# CTRL_POWER_OVER_ETHERNET.net
KiCad netlist of a schematic drawn in Altium Designer
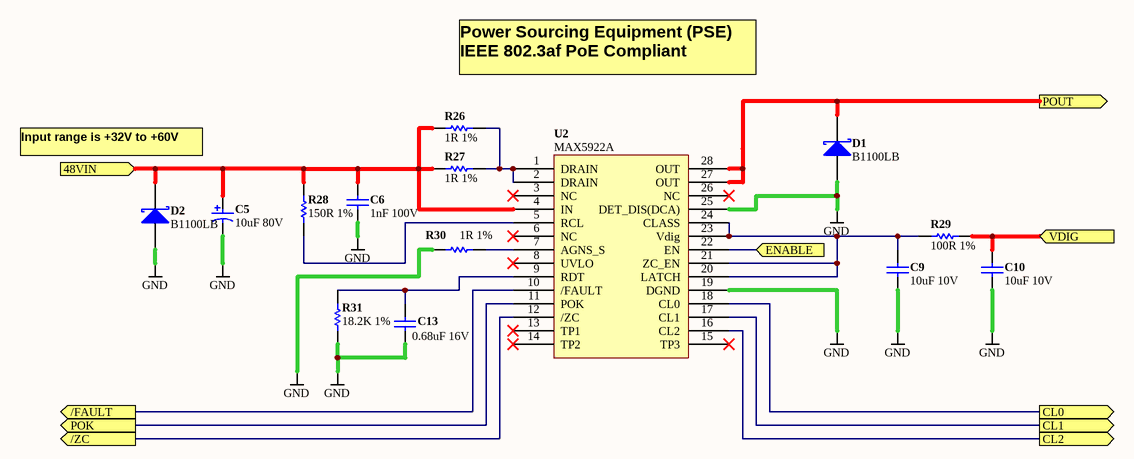
[diagram p0: CTRL_POWER_OVER_ETHERNET.SchDoc]

(export (version "E")
  (design (tool "Eeschema 10.0.6"))
  (components
    (comp (ref "C5")
      (value "10uF 80V")
      (footprint "CAP_FK_E_ELECTRO")
      (description "Capacitor, Electro, SMD, 80V, 10uF, Case E")
      (fields (field (name "TOLERANCE") "20 %"))
      (libsource (lib "AltiumDesignLibrary") (part "CAP-P"))
    )
    (comp (ref "C6")
      (value "1nF 100V")
      (footprint "CAPC2012-STAR")
      (description "Capacitor, Ceramic, 1nF, 100V, 0805, X7R")
      (fields (field (name "TOLERANCE") "%"))
      (libsource (lib "AltiumDesignLibrary") (part "CAP-NP"))
    )
    (comp (ref "C9")
      (value "10uF 10V")
      (footprint "CAPC2012-STAR")
      (description "Capacitor, Ceramic, 10uF 10% 10V 0805 (2012) X5R")
      (fields (field (name "TOLERANCE") "10 %"))
      (libsource (lib "AltiumDesignLibrary") (part "CAP-NP"))
    )
    (comp (ref "C10")
      (value "10uF 10V")
      (footprint "CAPC2012-STAR")
      (description "Capacitor, Ceramic, 10uF 10% 10V 0805 (2012) X5R")
      (fields (field (name "TOLERANCE") "10 %"))
      (libsource (lib "AltiumDesignLibrary") (part "CAP-NP"))
    )
    (comp (ref "C13")
      (value "0.68uF 16V")
      (footprint "CAPC1608-STAR")
      (description "Capacitor, Ceramic, 0.68uF 20% 16V 0603 X5R")
      (fields (field (name "TOLERANCE") "20 %"))
      (libsource (lib "AltiumDesignLibrary") (part "CAP-NP"))
    )
    (comp (ref "D1")
      (value "B1100LB")
      (footprint "DIOM8059")
      (description "Schottky Diode, 1A, 100V, SMB, B1100LB")
      (libsource (lib "AltiumDesignLibrary") (part "DIO-SCHOTTKY-1S"))
    )
    (comp (ref "D2")
      (value "B1100LB")
      (footprint "DIOM8059")
      (description "Schottky Diode, 1A, 100V, SMB, B1100LB")
      (libsource (lib "AltiumDesignLibrary") (part "DIO-SCHOTTKY-1S"))
    )
    (comp (ref "R26")
      (value "1R 1%")
      (footprint "RESC2012-STAR")
      (description "Resistor, 1R 1% 0805 (2012)")
      (fields (field (name "TOLERANCE") "1 %"))
      (libsource (lib "AltiumDesignLibrary") (part "RES"))
    )
    (comp (ref "R27")
      (value "1R 1%")
      (footprint "RESC2012-STAR")
      (description "Resistor, 1R 1% 0805 (2012)")
      (fields (field (name "TOLERANCE") "1 %"))
      (libsource (lib "AltiumDesignLibrary") (part "RES"))
    )
    (comp (ref "R28")
      (value "150R 1%")
      (footprint "RESC1005-STAR")
      (description "Resistor, 150R 1% 0402 (1005)")
      (fields (field (name "TOLERANCE") "1 %"))
      (libsource (lib "AltiumDesignLibrary") (part "RES"))
    )
    (comp (ref "R29")
      (value "100R 1%")
      (footprint "RESC1005-STAR")
      (description "Resistor, 100R 1% 0402 (1005)")
      (fields (field (name "TOLERANCE") "1 %"))
      (libsource (lib "AltiumDesignLibrary") (part "RES"))
    )
    (comp (ref "R30")
      (value "1R 1%")
      (footprint "RESC2012-STAR")
      (description "Resistor, 1R 1% 0805 (2012)")
      (fields (field (name "TOLERANCE") "1 %"))
      (libsource (lib "AltiumDesignLibrary") (part "RES"))
    )
    (comp (ref "R31")
      (value "18.2K 1%")
      (footprint "RESC1005-STAR")
      (description "Resistor, 18.2K 1% 0402 (1005)")
      (fields (field (name "TOLERANCE") "1 %"))
      (libsource (lib "AltiumDesignLibrary") (part "RES"))
    )
    (comp (ref "U2")
      (value "MAX5922A")
      (footprint "TSOP65P640-28")
      (description "MAX5922A, PoE Controller")
      (libsource (lib "AltiumDesignLibrary") (part "MAX5922"))
    )
  )
  (nets
    (net (code "1") (name "/48VIN") (class "Default")
      (node (ref "C5") (pin "1") (pinfunction "1_1") (pintype "passive"))
      (node (ref "C6") (pin "1") (pinfunction "1_1") (pintype "passive"))
      (node (ref "D2") (pin "2") (pinfunction "K_2") (pintype "passive"))
      (node (ref "R26") (pin "1") (pinfunction "1_1") (pintype "passive"))
      (node (ref "R27") (pin "1") (pinfunction "1_1") (pintype "passive"))
      (node (ref "R28") (pin "1") (pinfunction "1_1") (pintype "passive"))
      (node (ref "U2") (pin "4") (pinfunction "IN_4") (pintype "passive"))
    )
    (net (code "2") (name "/CL0") (class "Default")
      (node (ref "U2") (pin "18") (pinfunction "CL0_18") (pintype "passive"))
    )
    (net (code "3") (name "/CL1") (class "Default")
      (node (ref "U2") (pin "17") (pinfunction "CL1_17") (pintype "passive"))
    )
    (net (code "4") (name "/CL2") (class "Default")
      (node (ref "U2") (pin "16") (pinfunction "CL2_16") (pintype "passive"))
    )
    (net (code "5") (name "/ENABLE") (class "Default")
      (node (ref "U2") (pin "22") (pinfunction "EN_22") (pintype "passive"))
    )
    (net (code "6") (name "/POK") (class "Default")
      (node (ref "U2") (pin "11") (pinfunction "POK_11") (pintype "passive"))
    )
    (net (code "7") (name "/POUT") (class "Default")
      (node (ref "D1") (pin "2") (pinfunction "K_2") (pintype "passive"))
      (node (ref "U2") (pin "27") (pinfunction "OUT_27") (pintype "passive"))
      (node (ref "U2") (pin "28") (pinfunction "OUT_28") (pintype "passive"))
    )
    (net (code "8") (name "/VDIG") (class "Default")
      (node (ref "C10") (pin "1") (pinfunction "1_1") (pintype "passive"))
      (node (ref "R29") (pin "2") (pinfunction "2_2") (pintype "passive"))
    )
    (net (code "9") (name "/{slash}FAULT") (class "Default")
      (node (ref "U2") (pin "10") (pinfunction "/FAULT_10") (pintype "passive"))
    )
    (net (code "10") (name "/{slash}ZC") (class "Default")
      (node (ref "U2") (pin "12") (pinfunction "/ZC_12") (pintype "passive"))
    )
    (net (code "11") (name "GND") (class "Default")
      (node (ref "C10") (pin "2") (pinfunction "2_2") (pintype "passive"))
      (node (ref "C13") (pin "2") (pinfunction "2_2") (pintype "passive"))
      (node (ref "C5") (pin "2") (pinfunction "2_2") (pintype "passive"))
      (node (ref "C6") (pin "2") (pinfunction "2_2") (pintype "passive"))
      (node (ref "C9") (pin "2") (pinfunction "2_2") (pintype "passive"))
      (node (ref "D1") (pin "1") (pinfunction "A_1") (pintype "passive"))
      (node (ref "D2") (pin "1") (pinfunction "A_1") (pintype "passive"))
      (node (ref "R30") (pin "2") (pinfunction "2_2") (pintype "passive"))
      (node (ref "R31") (pin "2") (pinfunction "2_2") (pintype "passive"))
      (node (ref "U2") (pin "19") (pinfunction "DGND_19") (pintype "passive"))
      (node (ref "U2") (pin "25") (pinfunction "DET_DIS(DCA)_25") (pintype "passive"))
    )
    (net (code "12") (name "Net-(R26-Pad2)") (class "Default")
      (node (ref "R26") (pin "2") (pinfunction "2_2") (pintype "passive"))
      (node (ref "R27") (pin "2") (pinfunction "2_2") (pintype "passive"))
      (node (ref "U2") (pin "1") (pinfunction "DRAIN_1") (pintype "passive"))
      (node (ref "U2") (pin "2") (pinfunction "DRAIN_2") (pintype "passive"))
    )
    (net (code "13") (name "Net-(U2-AGNS_S)") (class "Default")
      (node (ref "R30") (pin "1") (pinfunction "1_1") (pintype "passive"))
      (node (ref "U2") (pin "7") (pinfunction "AGNS_S_7") (pintype "passive"))
    )
    (net (code "14") (name "Net-(U2-CLASS)") (class "Default")
      (node (ref "C9") (pin "1") (pinfunction "1_1") (pintype "passive"))
      (node (ref "R29") (pin "1") (pinfunction "1_1") (pintype "passive"))
      (node (ref "U2") (pin "20") (pinfunction "LATCH_20") (pintype "passive"))
      (node (ref "U2") (pin "21") (pinfunction "ZC_EN_21") (pintype "passive"))
      (node (ref "U2") (pin "23") (pinfunction "Vdig_23") (pintype "passive"))
      (node (ref "U2") (pin "24") (pinfunction "CLASS_24") (pintype "passive"))
    )
    (net (code "15") (name "Net-(U2-RCL)") (class "Default")
      (node (ref "R28") (pin "2") (pinfunction "2_2") (pintype "passive"))
      (node (ref "U2") (pin "5") (pinfunction "RCL_5") (pintype "passive"))
    )
    (net (code "16") (name "Net-(U2-RDT)") (class "Default")
      (node (ref "C13") (pin "1") (pinfunction "1_1") (pintype "passive"))
      (node (ref "R31") (pin "1") (pinfunction "1_1") (pintype "passive"))
      (node (ref "U2") (pin "9") (pinfunction "RDT_9") (pintype "passive"))
    )
    (net (code "17") (name "unconnected-(U2-NC-Pad3)") (class "Default")
      (node (ref "U2") (pin "3") (pinfunction "NC_3") (pintype "passive+no_connect"))
    )
    (net (code "18") (name "unconnected-(U2-NC-Pad6)") (class "Default")
      (node (ref "U2") (pin "6") (pinfunction "NC_6") (pintype "passive+no_connect"))
    )
    (net (code "19") (name "unconnected-(U2-NC-Pad26)") (class "Default")
      (node (ref "U2") (pin "26") (pinfunction "NC_26") (pintype "passive+no_connect"))
    )
    (net (code "20") (name "unconnected-(U2-TP1-Pad13)") (class "Default")
      (node (ref "U2") (pin "13") (pinfunction "TP1_13") (pintype "passive+no_connect"))
    )
    (net (code "21") (name "unconnected-(U2-TP2-Pad14)") (class "Default")
      (node (ref "U2") (pin "14") (pinfunction "TP2_14") (pintype "passive+no_connect"))
    )
    (net (code "22") (name "unconnected-(U2-TP3-Pad15)") (class "Default")
      (node (ref "U2") (pin "15") (pinfunction "TP3_15") (pintype "passive+no_connect"))
    )
    (net (code "23") (name "unconnected-(U2-UVLO-Pad8)") (class "Default")
      (node (ref "U2") (pin "8") (pinfunction "UVLO_8") (pintype "passive+no_connect"))
    )
  )
)
